# 2_LDO.net
KiCad netlist of a schematic drawn in Altium Designer
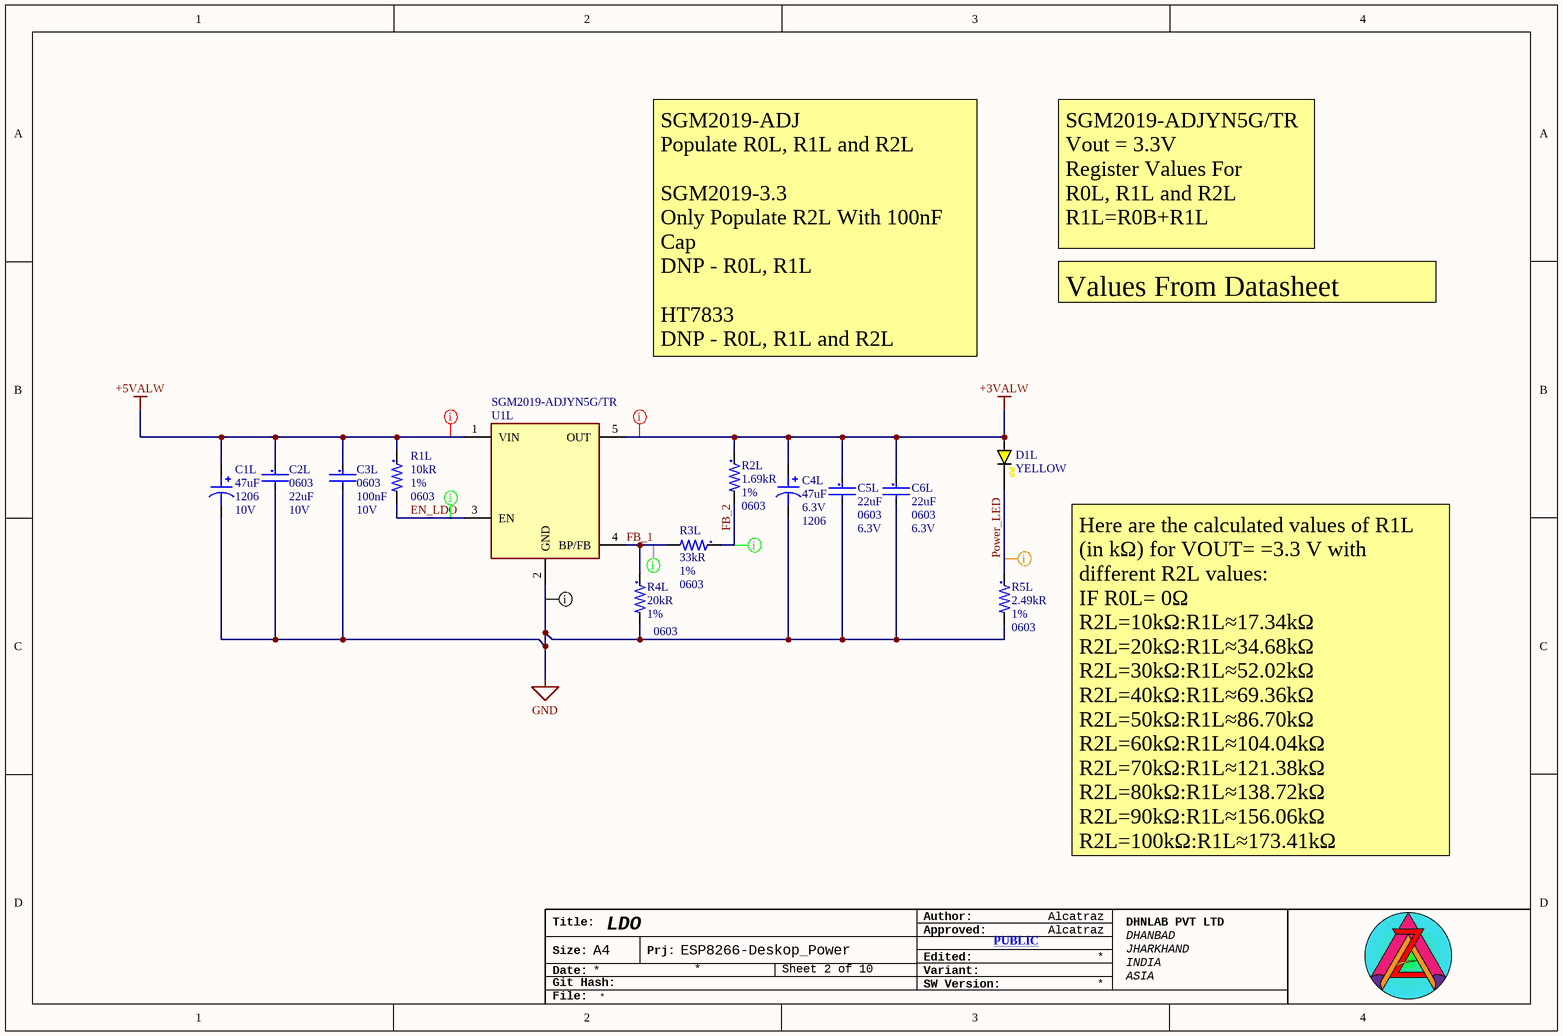
[diagram p0: 2_LDO.SchDoc]

(export (version "E")
  (design (tool "Eeschema 10.0.6"))
  (components
    (comp (ref "C1L")
      (value "47uF")
      (footprint "CAP POL 1206_3216-MFG")
      (description "Surface Mount Tantalum Capacitor, 47 uF, 10 V, ± 20%, -55 °C, 125 °C, 1206 [3216-12 Metric]")
      (fields
        (field (name "MANUFACTURER") "Rohm")
        (field (name "MANUFACTURER PART NUMBER") "TCTAL1A476M8R")
        (field (name "CASE/PACKAGE") "1206")
        (field (name "VOLTAGE RATING (DC)") "10V")
      )
      (libsource (lib "Lib_Capacitor_1206_Polarised") (part "47uF_10V"))
    )
    (comp (ref "C2L")
      (value "22uF")
      (footprint "C0603-IPC_C_No_Silk")
      (description "Multilayer Ceramic Capacitor, 22 uF, 10 V, ± 20%, X5R, 0603 [1608 Metric]")
      (fields
        (field (name "MANUFACTURER") "Murata")
        (field (name "MANUFACTURER PART NUMBER") "GRM188R61A226ME15D")
        (field (name "CASE/PACKAGE") "0603")
        (field (name "VOLTAGE RATING") "10V")
      )
      (libsource (lib "Lib_Capacitor_0603") (part "22uF_10V"))
    )
    (comp (ref "C3L")
      (value "100nF")
      (footprint "C0603-IPC_C_No_Silk")
      (description "Multilayer Ceramic Capacitor, 0.1 uF, 10 V, ± 10%, X7R, 0603 [1608 Metric]")
      (fields
        (field (name "MANUFACTURER") "KEMET")
        (field (name "MANUFACTURER PART NUMBER") "C0603C104K8RACTU")
        (field (name "CASE/PACKAGE") "0603")
        (field (name "VOLTAGE RATING") "10V")
      )
      (libsource (lib "Lib_Capacitor_0603") (part "100nF_10V"))
    )
    (comp (ref "C4L")
      (value "47uF")
      (footprint "CAP POL 1206_3216-MFG")
      (description "47uF Solid MnO2 Tantalum Electrolytic Capacitor; 6.3 V dc +/-20%; T491 Series")
      (fields
        (field (name "MANUFACTURER") "KEMET")
        (field (name "VOLTAGE") "6.3V")
        (field (name "SIZE") "1206")
        (field (name "MANUFACTURER PART NUMBER") "T491A476M006AT")
      )
      (libsource (lib "Lib_Capacitor_1206_Polarised") (part "47uF_6.3V"))
    )
    (comp (ref "C5L")
      (value "22uF")
      (footprint "C0603-IPC_C_No_Silk")
      (description "Multilayer Ceramic Capacitor, 22 uF, 6.3 V, ± 20%, X5R, 0603 [1608 Metric]")
      (fields
        (field (name "MANUFACTURER") "Murata")
        (field (name "MANUFACTURER PART NUMBER") "GRM188R60J226MEA0D")
        (field (name "CASE/PACKAGE") "0603")
        (field (name "VOLTAGE RATING") "6.3V")
      )
      (libsource (lib "Lib_Capacitor_0603") (part "22uF_6.3V"))
    )
    (comp (ref "C6L")
      (value "22uF")
      (footprint "C0603-IPC_C_No_Silk")
      (description "Multilayer Ceramic Capacitor, 22 uF, 6.3 V, ± 20%, X5R, 0603 [1608 Metric]")
      (fields
        (field (name "MANUFACTURER") "Murata")
        (field (name "MANUFACTURER PART NUMBER") "GRM188R60J226MEA0D")
        (field (name "CASE/PACKAGE") "0603")
        (field (name "VOLTAGE RATING") "6.3V")
      )
      (libsource (lib "Lib_Capacitor_0603") (part "22uF_6.3V"))
    )
    (comp (ref "D1L")
      (value "YELLOW")
      (footprint "LED_0603_YELLOW")
      (description "LED 0603 YELLOW SMD")
      (libsource (lib "Lib_LED") (part "LED_0603_YELLOW"))
    )
    (comp (ref "R1L")
      (value "10kR")
      (footprint "R0603-MFG")
      (description "SMD Chip Resistor, 10 kOhm, ± 1%, 100 mW, 0603 [1608 Metric], Thick Film, General Purpose")
      (fields
        (field (name "MANUFACTURER") "Yageo")
        (field (name "MANUFACTURER PART NUMBER") "RC0603FR-0710KL")
        (field (name "TOLERANCE") "1%")
        (field (name "CASE/PACKAGE") "0603")
      )
      (libsource (lib "Lib_Register_0603") (part "10K"))
    )
    (comp (ref "R2L")
      (value "1.69kR")
      (footprint "R0603-MFG")
      (description "Surface Mount Thick Film Chip Resistor 0603 Case 1.69K Ohms 1% Tolerance 100 PPM")
      (fields
        (field (name "MANUFACTURER") "Rohm")
        (field (name "MANUFACTURER PART NUMBER") "MCR03EZPFX1691")
        (field (name "TOLERANCE") "1%")
        (field (name "CASE/PACKAGE") "0603")
      )
      (libsource (lib "Lib_Register_0603") (part "1.69K"))
    )
    (comp (ref "R3L")
      (value "33kR")
      (footprint "R0603-MFG")
      (description "Res Thick Film 0603 33K Ohm 1% 0.1W(1/10W) ±100ppm/C Pad SMD Automotive T/R")
      (fields
        (field (name "MANUFACTURER") "Panasonic")
        (field (name "MANUFACTURER PART NUMBER") "ERJ-3EKF3302V")
        (field (name "TOLERANCE") "1%")
        (field (name "CASE/PACKAGE") "0603")
      )
      (libsource (lib "Lib_Register_0603") (part "33K"))
    )
    (comp (ref "R4L")
      (value "20kR")
      (footprint "R0603-MFG")
      (description "SMD Chip Resistor, 20 kOhm, ± 1%, 100 mW, 0603 [1608 Metric], Thick Film, General Purpose")
      (fields
        (field (name "MANUFACTURER") "Bourns")
        (field (name "MANUFACTURER PART NUMBER") "CR0603-FX-2002ELF")
        (field (name "TOLERANCE") "1%")
        (field (name "CASE/PACKAGE") "0603")
      )
      (libsource (lib "Lib_Register_0603") (part "20K"))
    )
    (comp (ref "R5L")
      (value "2.49kR")
      (footprint "R0603-MFG")
      (description "Res Thick Film 0603 2.49K Ohm 1% 1/10W ±100ppm/°C Molded SMD SMD Paper T/R")
      (fields
        (field (name "MANUFACTURER") "Rohm")
        (field (name "MANUFACTURER PART NUMBER") "MCR03EZPFX2491")
        (field (name "TOLERANCE") "1%")
        (field (name "CASE/PACKAGE") "0603")
      )
      (libsource (lib "Lib_Register_0603") (part "2.49K"))
    )
    (comp (ref "U1L")
      (value "SGM2019-ADJYN5G/TR")
      (footprint "TSOT-23-5-IPC-A")
      (description "LDO U-Reg Adj 0, 3A SOT23-5")
      (fields (field (name "MANUFACTURER") "SG Micro"))
      (libsource (lib "Lib_LDO") (part "SGM2019-ADJYN5G/TR"))
    )
  )
  (nets
    (net (code "1") (name "+3VALW") (class "Default")
      (node (ref "C4L") (pin "1") (pinfunction "1_1") (pintype "passive"))
      (node (ref "C5L") (pin "1") (pinfunction "1_1") (pintype "passive"))
      (node (ref "C6L") (pin "1") (pinfunction "1_1") (pintype "passive"))
      (node (ref "D1L") (pin "2") (pinfunction "A_2") (pintype "passive"))
      (node (ref "R2L") (pin "1") (pinfunction "1_1") (pintype "passive"))
      (node (ref "U1L") (pin "5") (pinfunction "OUT_5") (pintype "power_in"))
    )
    (net (code "2") (name "+5VALW") (class "Default")
      (node (ref "C1L") (pin "1") (pinfunction "1_1") (pintype "passive"))
      (node (ref "C2L") (pin "1") (pinfunction "1_1") (pintype "passive"))
      (node (ref "C3L") (pin "1") (pinfunction "1_1") (pintype "passive"))
      (node (ref "R1L") (pin "1") (pinfunction "1_1") (pintype "passive"))
      (node (ref "U1L") (pin "1") (pinfunction "VIN_1") (pintype "power_in"))
    )
    (net (code "3") (name "/EN_LDO") (class "Default")
      (node (ref "R1L") (pin "2") (pinfunction "2_2") (pintype "passive"))
      (node (ref "U1L") (pin "3") (pinfunction "EN_3") (pintype "passive"))
    )
    (net (code "4") (name "/FB_1") (class "Default")
      (node (ref "R3L") (pin "2") (pinfunction "2_2") (pintype "passive"))
      (node (ref "R4L") (pin "1") (pinfunction "1_1") (pintype "passive"))
      (node (ref "U1L") (pin "4") (pinfunction "BP/FB_4") (pintype "passive"))
    )
    (net (code "5") (name "/FB_2") (class "Default")
      (node (ref "R2L") (pin "2") (pinfunction "2_2") (pintype "passive"))
      (node (ref "R3L") (pin "1") (pinfunction "1_1") (pintype "passive"))
    )
    (net (code "6") (name "/Power_LED") (class "Default")
      (node (ref "D1L") (pin "1") (pinfunction "K_1") (pintype "passive"))
      (node (ref "R5L") (pin "1") (pinfunction "1_1") (pintype "passive"))
    )
    (net (code "7") (name "GND") (class "Default")
      (node (ref "C1L") (pin "2") (pinfunction "2_2") (pintype "passive"))
      (node (ref "C2L") (pin "2") (pinfunction "2_2") (pintype "passive"))
      (node (ref "C3L") (pin "2") (pinfunction "2_2") (pintype "passive"))
      (node (ref "C4L") (pin "2") (pinfunction "2_2") (pintype "passive"))
      (node (ref "C5L") (pin "2") (pinfunction "2_2") (pintype "passive"))
      (node (ref "C6L") (pin "2") (pinfunction "2_2") (pintype "passive"))
      (node (ref "R4L") (pin "2") (pinfunction "2_2") (pintype "passive"))
      (node (ref "R5L") (pin "2") (pinfunction "2_2") (pintype "passive"))
      (node (ref "U1L") (pin "2") (pinfunction "GND_2") (pintype "power_in"))
    )
  )
)
